# Power.net
KiCad netlist of a schematic drawn in Altium Designer
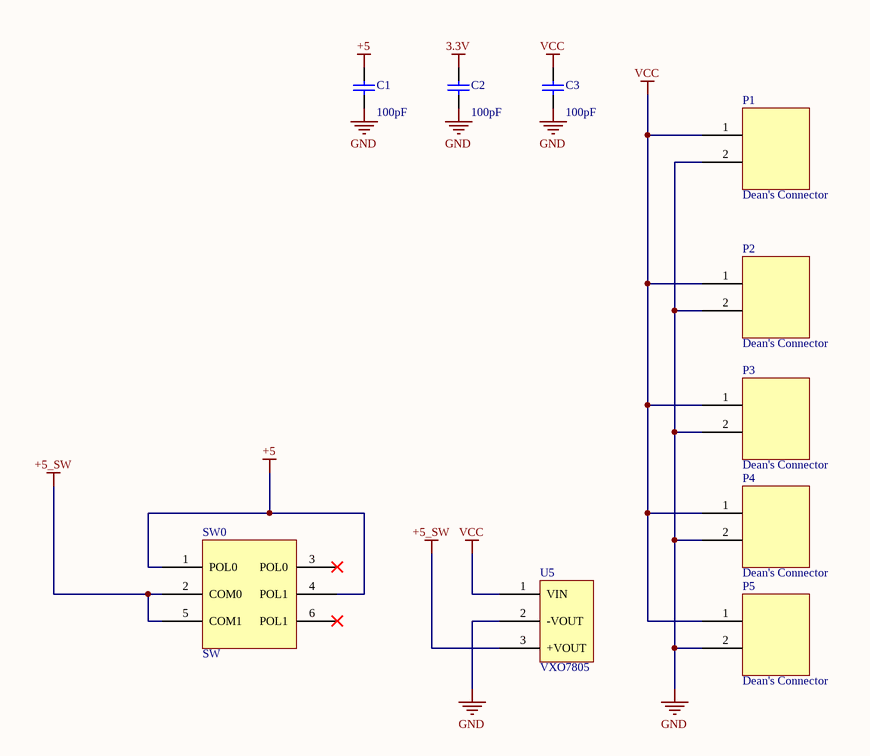
[diagram p0: Power.SchDoc]

(export (version "E")
  (design (tool "Eeschema 10.0.6"))
  (components
    (comp (ref "C1")
      (value "100pF")
      (footprint "C1206")
      (description "Capacitor (Semiconductor SIM Model)")
      (fields (field (name "Comment") "Cap Semi") (field (name "PUBLISHER") "Altium Limited"))
      (libsource (lib "Miscellaneous Devices") (part "Cap Semi"))
    )
    (comp (ref "C2")
      (value "100pF")
      (footprint "C1206")
      (description "Capacitor (Semiconductor SIM Model)")
      (fields (field (name "Comment") "Cap Semi") (field (name "PUBLISHER") "Altium Limited"))
      (libsource (lib "Miscellaneous Devices") (part "Cap Semi"))
    )
    (comp (ref "C3")
      (value "100pF")
      (footprint "C1206")
      (description "Capacitor (Semiconductor SIM Model)")
      (fields (field (name "Comment") "Cap Semi") (field (name "PUBLISHER") "Altium Limited"))
      (libsource (lib "Miscellaneous Devices") (part "Cap Semi"))
    )
    (comp (ref "P1")
      (value "Dean's Connector")
      (footprint "DEAN_CONN")
      (libsource (lib "Quadrotor_Lib") (part "Dean's Connector"))
    )
    (comp (ref "P2")
      (value "Dean's Connector")
      (footprint "DEAN_CONN")
      (libsource (lib "Quadrotor_Lib") (part "Dean's Connector"))
    )
    (comp (ref "P3")
      (value "Dean's Connector")
      (footprint "DEAN_CONN")
      (libsource (lib "Quadrotor_Lib") (part "Dean's Connector"))
    )
    (comp (ref "P4")
      (value "Dean's Connector")
      (footprint "DEAN_CONN")
      (libsource (lib "Quadrotor_Lib") (part "Dean's Connector"))
    )
    (comp (ref "P5")
      (value "Dean's Connector")
      (footprint "DEAN_CONN")
      (libsource (lib "Quadrotor_Lib") (part "Dean's Connector"))
    )
    (comp (ref "SW0") (value "SW") (footprint "SW") (libsource (lib "Quadrotor_Lib") (part "SW")))
    (comp (ref "U5")
      (value "VXO7805")
      (footprint "VXO78-1000")
      (libsource (lib "Quadrotor_Lib") (part "VXO7805"))
    )
  )
  (nets
    (net (code "1") (name "+5") (class "Default")
      (node (ref "C1") (pin "2") (pinfunction "2_2") (pintype "passive"))
      (node (ref "SW0") (pin "1") (pinfunction "POL0_1") (pintype "passive"))
      (node (ref "SW0") (pin "4") (pinfunction "POL1_4") (pintype "passive"))
    )
    (net (code "2") (name "+5_SW") (class "Default")
      (node (ref "SW0") (pin "2") (pinfunction "COM0_2") (pintype "passive"))
      (node (ref "SW0") (pin "5") (pinfunction "COM1_5") (pintype "passive"))
      (node (ref "U5") (pin "3") (pinfunction "+VOUT_3") (pintype "passive"))
    )
    (net (code "3") (name "3.3V") (class "Default")
      (node (ref "C2") (pin "2") (pinfunction "2_2") (pintype "passive"))
    )
    (net (code "4") (name "GND") (class "Default")
      (node (ref "C1") (pin "1") (pinfunction "1_1") (pintype "passive"))
      (node (ref "C2") (pin "1") (pinfunction "1_1") (pintype "passive"))
      (node (ref "C3") (pin "1") (pinfunction "1_1") (pintype "passive"))
      (node (ref "P1") (pin "2") (pintype "power_in"))
      (node (ref "P2") (pin "2") (pintype "power_in"))
      (node (ref "P3") (pin "2") (pintype "power_in"))
      (node (ref "P4") (pin "2") (pintype "power_in"))
      (node (ref "P5") (pin "2") (pintype "power_in"))
      (node (ref "U5") (pin "2") (pinfunction "-VOUT_2") (pintype "passive"))
    )
    (net (code "5") (name "VCC") (class "Default")
      (node (ref "C3") (pin "2") (pinfunction "2_2") (pintype "passive"))
      (node (ref "P1") (pin "1") (pintype "power_in"))
      (node (ref "P2") (pin "1") (pintype "power_in"))
      (node (ref "P3") (pin "1") (pintype "power_in"))
      (node (ref "P4") (pin "1") (pintype "power_in"))
      (node (ref "P5") (pin "1") (pintype "power_in"))
      (node (ref "U5") (pin "1") (pinfunction "VIN_1") (pintype "passive"))
    )
    (net (code "6") (name "unconnected-(SW0-POL0-Pad3)") (class "Default")
      (node (ref "SW0") (pin "3") (pinfunction "POL0_3") (pintype "passive+no_connect"))
    )
    (net (code "7") (name "unconnected-(SW0-POL1-Pad6)") (class "Default")
      (node (ref "SW0") (pin "6") (pinfunction "POL1_6") (pintype "passive+no_connect"))
    )
  )
)
